# QEA_Interface.net
KiCad netlist of a schematic drawn in Altium Designer
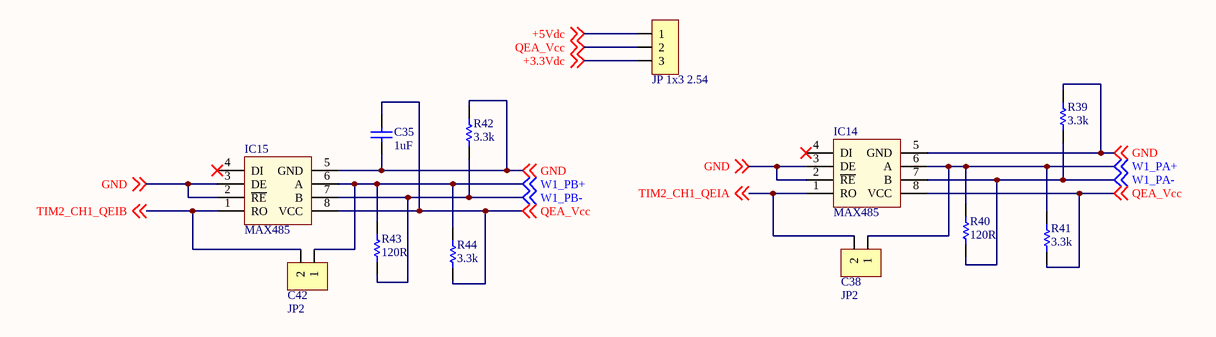
[diagram p0: QEA_Interface.SchDoc]

(export (version "E")
  (design (tool "Eeschema 10.0.6"))
  (components
    (comp (ref "C35")
      (value "1uF")
      (footprint "tu 0603")
      (description "Dán")
      (libsource (lib "Tu dien") (part "Tu 0603 102 50V 10%"))
    )
    (comp (ref "C38")
      (value "JP2")
      (footprint "JP2-CLOSED")
      (description "WR-PHD 2.54 mm Angled Socket Header")
      (fields
        (field (name "MANUFACTURER") "Würth Elektronik eiSos GmbH")
        (field (name "PARTNO") "613002143121")
        (field (name "CREATED BY") "Karrer Zheng")
      )
      (libsource (lib "LIBRARY") (part "JP2"))
    )
    (comp (ref "C42")
      (value "JP2")
      (footprint "JP2-CLOSED")
      (description "WR-PHD 2.54 mm Angled Socket Header")
      (fields
        (field (name "MANUFACTURER") "Würth Elektronik eiSos GmbH")
        (field (name "PARTNO") "613002143121")
        (field (name "CREATED BY") "Karrer Zheng")
      )
      (libsource (lib "LIBRARY") (part "JP2"))
    )
    (comp (ref "IC14")
      (value "MAX485")
      (footprint "SO8")
      (description "RS232 - RS485 (Same sn75176)")
      (libsource (lib "LIBRARY") (part "MAX485"))
    )
    (comp (ref "IC15")
      (value "MAX485")
      (footprint "SO8")
      (description "RS232 - RS485 (Same sn75176)")
      (libsource (lib "LIBRARY") (part "MAX485"))
    )
    (comp (ref "JP4")
      (value "JP 1x3 2.54")
      (footprint "JP 1x3 DT")
      (description "Cắm")
      (libsource (lib "Jump") (part "JP 1x3 2.54 Duc Thang"))
    )
    (comp (ref "R39")
      (value "3.3k")
      (footprint "RES 0603")
      (description "Semiconductor Resistor")
      (fields (field (name "PUBLISHER") "Altium Limited"))
      (libsource (lib "DoHuong_sch") (part "Resistor"))
    )
    (comp (ref "R40")
      (value "120R")
      (footprint "RES 0603")
      (description "Semiconductor Resistor")
      (fields (field (name "PUBLISHER") "Altium Limited"))
      (libsource (lib "DoHuong_sch") (part "Resistor"))
    )
    (comp (ref "R41")
      (value "3.3k")
      (footprint "RES 0603")
      (description "Semiconductor Resistor")
      (fields (field (name "PUBLISHER") "Altium Limited"))
      (libsource (lib "DoHuong_sch") (part "Resistor"))
    )
    (comp (ref "R42")
      (value "3.3k")
      (footprint "RES 0603")
      (description "Semiconductor Resistor")
      (fields (field (name "PUBLISHER") "Altium Limited"))
      (libsource (lib "DoHuong_sch") (part "Resistor"))
    )
    (comp (ref "R43")
      (value "120R")
      (footprint "RES 0603")
      (description "Semiconductor Resistor")
      (fields (field (name "PUBLISHER") "Altium Limited"))
      (libsource (lib "DoHuong_sch") (part "Resistor"))
    )
    (comp (ref "R44")
      (value "3.3k")
      (footprint "RES 0603")
      (description "Semiconductor Resistor")
      (fields (field (name "PUBLISHER") "Altium Limited"))
      (libsource (lib "DoHuong_sch") (part "Resistor"))
    )
  )
  (nets
    (net (code "1") (name "+3.3Vdc") (class "Default")
      (node (ref "JP4") (pin "3") (pinfunction "3_3") (pintype "passive"))
    )
    (net (code "2") (name "+5Vdc") (class "Default")
      (node (ref "JP4") (pin "1") (pinfunction "1_1") (pintype "passive"))
    )
    (net (code "3") (name "GND") (class "Default")
      (node (ref "C35") (pin "1") (pinfunction "1_1") (pintype "passive"))
      (node (ref "IC14") (pin "2") (pinfunction "~{RE}_2") (pintype "passive"))
      (node (ref "IC14") (pin "3") (pinfunction "DE_3") (pintype "passive"))
      (node (ref "IC14") (pin "5") (pinfunction "GND_5") (pintype "passive"))
      (node (ref "IC15") (pin "2") (pinfunction "~{RE}_2") (pintype "passive"))
      (node (ref "IC15") (pin "3") (pinfunction "DE_3") (pintype "passive"))
      (node (ref "IC15") (pin "5") (pinfunction "GND_5") (pintype "passive"))
      (node (ref "R39") (pin "2") (pinfunction "2_2") (pintype "passive"))
      (node (ref "R42") (pin "2") (pinfunction "2_2") (pintype "passive"))
    )
    (net (code "4") (name "QEA_Vcc") (class "Default")
      (node (ref "C35") (pin "2") (pinfunction "2_2") (pintype "passive"))
      (node (ref "IC14") (pin "8") (pinfunction "VCC_8") (pintype "passive"))
      (node (ref "IC15") (pin "8") (pinfunction "VCC_8") (pintype "passive"))
      (node (ref "JP4") (pin "2") (pinfunction "2_2") (pintype "passive"))
      (node (ref "R41") (pin "1") (pinfunction "1_1") (pintype "passive"))
      (node (ref "R44") (pin "1") (pinfunction "1_1") (pintype "passive"))
    )
    (net (code "5") (name "TIM2_CH1_QEIA") (class "Default")
      (node (ref "C38") (pin "2") (pinfunction "2_2") (pintype "passive"))
      (node (ref "IC14") (pin "1") (pinfunction "RO_1") (pintype "passive"))
    )
    (net (code "6") (name "TIM2_CH1_QEIB") (class "Default")
      (node (ref "C42") (pin "2") (pinfunction "2_2") (pintype "passive"))
      (node (ref "IC15") (pin "1") (pinfunction "RO_1") (pintype "passive"))
    )
    (net (code "7") (name "W1_PA+") (class "Default")
      (node (ref "C38") (pin "1") (pinfunction "1_1") (pintype "passive"))
      (node (ref "IC14") (pin "6") (pinfunction "A_6") (pintype "passive"))
      (node (ref "R40") (pin "2") (pinfunction "2_2") (pintype "passive"))
      (node (ref "R41") (pin "2") (pinfunction "2_2") (pintype "passive"))
    )
    (net (code "8") (name "W1_PA-") (class "Default")
      (node (ref "IC14") (pin "7") (pinfunction "B_7") (pintype "passive"))
      (node (ref "R39") (pin "1") (pinfunction "1_1") (pintype "passive"))
      (node (ref "R40") (pin "1") (pinfunction "1_1") (pintype "passive"))
    )
    (net (code "9") (name "W1_PB+") (class "Default")
      (node (ref "C42") (pin "1") (pinfunction "1_1") (pintype "passive"))
      (node (ref "IC15") (pin "6") (pinfunction "A_6") (pintype "passive"))
      (node (ref "R43") (pin "2") (pinfunction "2_2") (pintype "passive"))
      (node (ref "R44") (pin "2") (pinfunction "2_2") (pintype "passive"))
    )
    (net (code "10") (name "W1_PB-") (class "Default")
      (node (ref "IC15") (pin "7") (pinfunction "B_7") (pintype "passive"))
      (node (ref "R42") (pin "1") (pinfunction "1_1") (pintype "passive"))
      (node (ref "R43") (pin "1") (pinfunction "1_1") (pintype "passive"))
    )
    (net (code "11") (name "unconnected-(IC14-DI-Pad4)") (class "Default")
      (node (ref "IC14") (pin "4") (pinfunction "DI_4") (pintype "passive+no_connect"))
    )
    (net (code "12") (name "unconnected-(IC15-DI-Pad4)") (class "Default")
      (node (ref "IC15") (pin "4") (pinfunction "DI_4") (pintype "passive+no_connect"))
    )
  )
)
